# sensor_connector.net
KiCad netlist of a schematic drawn in Altium Designer
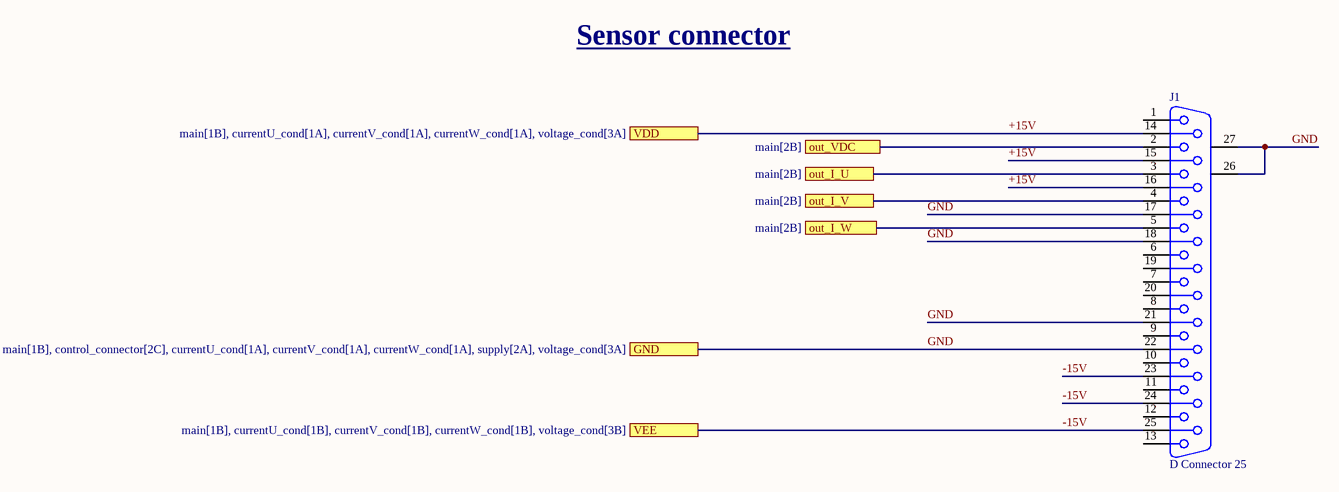
[diagram p0: sensor_connector.SchDoc]

(export (version "E")
  (design (tool "Eeschema 10.0.6"))
  (components
    (comp (ref "J1")
      (value "D Connector 25")
      (footprint "DSUB1.385-2H25A_mod")
      (description "Receptacle Assembly, 25 Position, Right Angle")
      (fields (field (name "PUBLISHER") "Altium Limited"))
      (libsource (lib "LABSTEPS_Project") (part "D Connector 25"))
    )
  )
  (nets
    (net (code "1") (name "/+15V") (class "Default")
      (node (ref "J1") (pin "14") (pinfunction "14_14") (pintype "passive"))
      (node (ref "J1") (pin "15") (pinfunction "15_15") (pintype "passive"))
      (node (ref "J1") (pin "16") (pinfunction "16_16") (pintype "passive"))
    )
    (net (code "2") (name "/-15V") (class "Default")
      (node (ref "J1") (pin "23") (pinfunction "23_23") (pintype "passive"))
      (node (ref "J1") (pin "24") (pinfunction "24_24") (pintype "passive"))
      (node (ref "J1") (pin "25") (pinfunction "25_25") (pintype "passive"))
    )
    (net (code "3") (name "/GND") (class "Default")
      (node (ref "J1") (pin "17") (pinfunction "17_17") (pintype "passive"))
      (node (ref "J1") (pin "18") (pinfunction "18_18") (pintype "passive"))
      (node (ref "J1") (pin "21") (pinfunction "21_21") (pintype "passive"))
      (node (ref "J1") (pin "22") (pinfunction "22_22") (pintype "passive"))
      (node (ref "J1") (pin "26") (pinfunction "MH1_26") (pintype "passive"))
      (node (ref "J1") (pin "27") (pinfunction "MH2_27") (pintype "passive"))
    )
    (net (code "4") (name "/out_I_U") (class "Default")
      (node (ref "J1") (pin "3") (pinfunction "3_3") (pintype "passive"))
    )
    (net (code "5") (name "/out_I_V") (class "Default")
      (node (ref "J1") (pin "4") (pinfunction "4_4") (pintype "passive"))
    )
    (net (code "6") (name "/out_I_W") (class "Default")
      (node (ref "J1") (pin "5") (pinfunction "5_5") (pintype "passive"))
    )
    (net (code "7") (name "/out_VDC") (class "Default")
      (node (ref "J1") (pin "2") (pinfunction "2_2") (pintype "passive"))
    )
    (net (code "8") (name "unconnected-(J1-Pad1)") (class "Default")
      (node (ref "J1") (pin "1") (pinfunction "1_1") (pintype "passive"))
    )
    (net (code "9") (name "unconnected-(J1-Pad6)") (class "Default")
      (node (ref "J1") (pin "6") (pinfunction "6_6") (pintype "passive"))
    )
    (net (code "10") (name "unconnected-(J1-Pad7)") (class "Default")
      (node (ref "J1") (pin "7") (pinfunction "7_7") (pintype "passive"))
    )
    (net (code "11") (name "unconnected-(J1-Pad8)") (class "Default")
      (node (ref "J1") (pin "8") (pinfunction "8_8") (pintype "passive"))
    )
    (net (code "12") (name "unconnected-(J1-Pad9)") (class "Default")
      (node (ref "J1") (pin "9") (pinfunction "9_9") (pintype "passive"))
    )
    (net (code "13") (name "unconnected-(J1-Pad10)") (class "Default")
      (node (ref "J1") (pin "10") (pinfunction "10_10") (pintype "passive"))
    )
    (net (code "14") (name "unconnected-(J1-Pad11)") (class "Default")
      (node (ref "J1") (pin "11") (pinfunction "11_11") (pintype "passive"))
    )
    (net (code "15") (name "unconnected-(J1-Pad12)") (class "Default")
      (node (ref "J1") (pin "12") (pinfunction "12_12") (pintype "passive"))
    )
    (net (code "16") (name "unconnected-(J1-Pad13)") (class "Default")
      (node (ref "J1") (pin "13") (pinfunction "13_13") (pintype "passive"))
    )
    (net (code "17") (name "unconnected-(J1-Pad19)") (class "Default")
      (node (ref "J1") (pin "19") (pinfunction "19_19") (pintype "passive"))
    )
    (net (code "18") (name "unconnected-(J1-Pad20)") (class "Default")
      (node (ref "J1") (pin "20") (pinfunction "20_20") (pintype "passive"))
    )
  )
)
